# mcu_core.net
KiCad netlist of a schematic drawn in Altium Designer
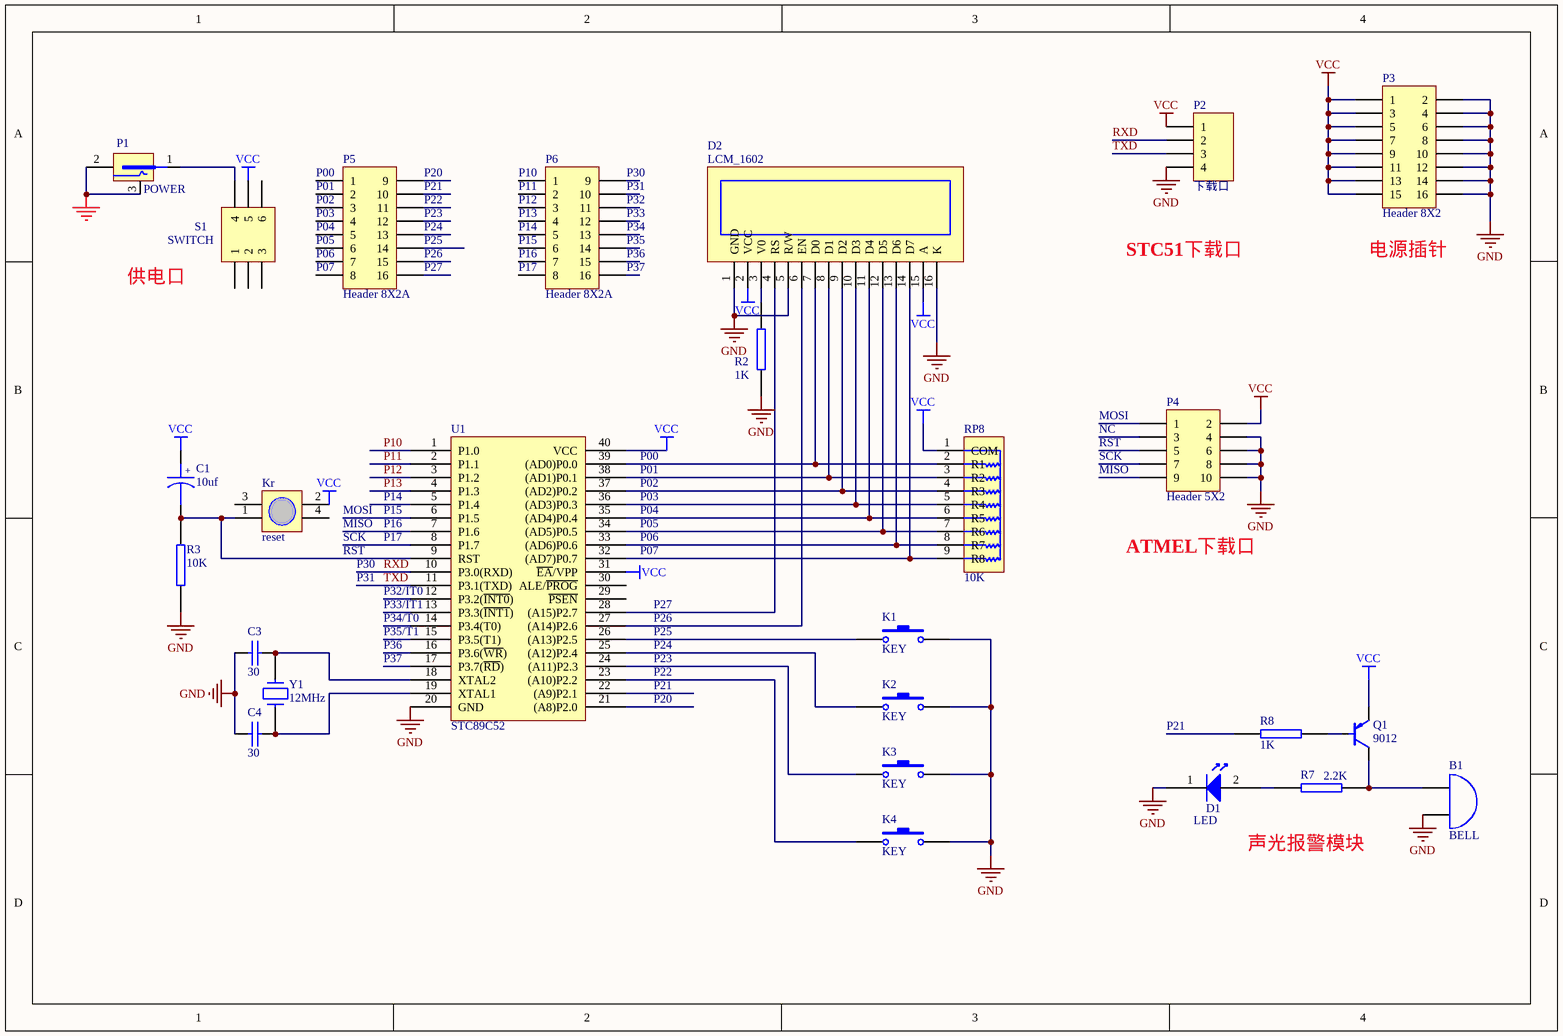
[diagram p0: mcu core.SchDoc]

(export (version "E")
  (design (tool "Eeschema 10.0.6"))
  (components
    (comp (ref "B1") (value "BELL") (footprint "bell") (libsource (lib "xinweidz") (part "BELL")))
    (comp (ref "C1")
      (value "10uf")
      (footprint "C4*7")
      (description "Capacitor")
      (libsource (lib "xinweidz") (part "电解电容"))
    )
    (comp (ref "C3")
      (value "30")
      (footprint "CAP-2.54")
      (description "Capacitor")
      (libsource (lib "*") (part "CAP"))
    )
    (comp (ref "C4")
      (value "30")
      (footprint "CAP-2.54")
      (description "Capacitor")
      (libsource (lib "*") (part "CAP"))
    )
    (comp (ref "D1") (value "LED") (footprint "LED5MM-RED") (libsource (lib "xinweidz") (part "LED5")))
    (comp (ref "D2") (value "LCM_1602") (footprint "HDR1X16") (libsource (lib "*") (part "LCM1602")))
    (comp (ref "K1")
      (value "KEY")
      (footprint "SW-0606")
      (fields (field (name "PUBLISHER") "Altium Limited"))
      (libsource (lib "BIG_PP") (part "KEY"))
    )
    (comp (ref "K2")
      (value "KEY")
      (footprint "SW-0606")
      (fields (field (name "PUBLISHER") "Altium Limited"))
      (libsource (lib "BIG_PP") (part "KEY"))
    )
    (comp (ref "K3")
      (value "KEY")
      (footprint "SW-0606")
      (fields (field (name "PUBLISHER") "Altium Limited"))
      (libsource (lib "BIG_PP") (part "KEY"))
    )
    (comp (ref "K4")
      (value "KEY")
      (footprint "SW-0606")
      (fields (field (name "PUBLISHER") "Altium Limited"))
      (libsource (lib "BIG_PP") (part "KEY"))
    )
    (comp (ref "Kr") (value "reset") (footprint "SW-0606") (libsource (lib "*") (part "KEY")))
    (comp (ref "P1") (value "POWER") (footprint "DC002") (libsource (lib "*") (part "POWER")))
    (comp (ref "P2")
      (value "下载口")
      (footprint "HDR1X4")
      (description "Header, 4-Pin, Right Angle")
      (fields (field (name "PUBLISHER") "Altium Limited"))
      (libsource (lib "BIG_PP") (part "Header 4H"))
    )
    (comp (ref "P3")
      (value "Header 8X2")
      (footprint "HDR2X8")
      (description "Header, 8-Pin, Dual row")
      (fields (field (name "PUBLISHER") "Altium Limited"))
      (libsource (lib "BIG_PP") (part "Header 8X2"))
    )
    (comp (ref "P4")
      (value "Header 5X2")
      (footprint "HDR2X5")
      (description "Header, 5-Pin, Dual row")
      (fields (field (name "PUBLISHER") "Altium Limited"))
      (libsource (lib "BIG_PP") (part "Header 5X2"))
    )
    (comp (ref "P5")
      (value "Header 8X2A")
      (footprint "HDR2X8_CEN")
      (description "Header, 8-Pin, Dual row")
      (fields (field (name "PUBLISHER") "Altium Limited"))
      (libsource (lib "BIG_PP") (part "Header 8X2A"))
    )
    (comp (ref "P6")
      (value "Header 8X2A")
      (footprint "HDR2X8_CEN")
      (description "Header, 8-Pin, Dual row")
      (fields (field (name "PUBLISHER") "Altium Limited"))
      (libsource (lib "BIG_PP") (part "Header 8X2A"))
    )
    (comp (ref "Q1") (value "9012") (footprint "TO-92A") (libsource (lib "xinweidz") (part "PNP")))
    (comp (ref "R2") (value "1K") (footprint "1/4W") (libsource (lib "*") (part "RES2")))
    (comp (ref "R3") (value "10K") (footprint "1/4W") (libsource (lib "*") (part "RES2")))
    (comp (ref "R7") (value "2.2K") (footprint "1/4W") (libsource (lib "*") (part "RES2")))
    (comp (ref "R8") (value "1K") (footprint "1/4W") (libsource (lib "*") (part "RES2")))
    (comp (ref "RP8") (value "10K") (footprint "R-9PIN") (libsource (lib "*") (part "RP8")))
    (comp (ref "S1")
      (value "SWITCH")
      (footprint "SW-8X8X8")
      (description "Header, 3-Pin, Dual row")
      (fields (field (name "PUBLISHER") "Altium Limited"))
      (libsource (lib "BIG_PP") (part "Header 3X2A"))
    )
    (comp (ref "U1") (value "STC89C52") (footprint "DIP40") (libsource (lib "*") (part "AT89C51")))
    (comp (ref "Y1")
      (value "12MHz")
      (footprint "XTAL-49/S_N")
      (description "Crystal")
      (libsource (lib "*") (part "CRYSTAL"))
    )
  )
  (nets
    (net (code "1") (name "/MISO") (class "Default")
      (node (ref "P4") (pin "9") (pinfunction "9_9") (pintype "passive"))
      (node (ref "P6") (pin "7") (pinfunction "7_7") (pintype "passive"))
      (node (ref "U1") (pin "7") (pinfunction "P1.6_7") (pintype "passive"))
    )
    (net (code "2") (name "/MOSI") (class "Default")
      (node (ref "P4") (pin "1") (pinfunction "1_1") (pintype "passive"))
      (node (ref "P6") (pin "6") (pinfunction "6_6") (pintype "passive"))
      (node (ref "U1") (pin "6") (pinfunction "P1.5_6") (pintype "passive"))
    )
    (net (code "3") (name "/NC") (class "Default")
      (node (ref "P4") (pin "3") (pinfunction "3_3") (pintype "passive"))
    )
    (net (code "4") (name "/P00") (class "Default")
      (node (ref "D2") (pin "7") (pinfunction "D0_7") (pintype "passive"))
      (node (ref "P5") (pin "1") (pinfunction "1_1") (pintype "passive"))
      (node (ref "RP8") (pin "2") (pinfunction "R1_2") (pintype "passive"))
      (node (ref "U1") (pin "39") (pinfunction "(AD0)P0.0_39") (pintype "passive"))
    )
    (net (code "5") (name "/P01") (class "Default")
      (node (ref "D2") (pin "8") (pinfunction "D1_8") (pintype "passive"))
      (node (ref "P5") (pin "2") (pinfunction "2_2") (pintype "passive"))
      (node (ref "RP8") (pin "3") (pinfunction "R2_3") (pintype "passive"))
      (node (ref "U1") (pin "38") (pinfunction "(AD1)P0.1_38") (pintype "passive"))
    )
    (net (code "6") (name "/P02") (class "Default")
      (node (ref "D2") (pin "9") (pinfunction "D2_9") (pintype "passive"))
      (node (ref "P5") (pin "3") (pinfunction "3_3") (pintype "passive"))
      (node (ref "RP8") (pin "4") (pinfunction "R3_4") (pintype "passive"))
      (node (ref "U1") (pin "37") (pinfunction "(AD2)P0.2_37") (pintype "passive"))
    )
    (net (code "7") (name "/P03") (class "Default")
      (node (ref "D2") (pin "10") (pinfunction "D3_10") (pintype "passive"))
      (node (ref "P5") (pin "4") (pinfunction "4_4") (pintype "passive"))
      (node (ref "RP8") (pin "5") (pinfunction "R4_5") (pintype "passive"))
      (node (ref "U1") (pin "36") (pinfunction "(AD3)P0.3_36") (pintype "passive"))
    )
    (net (code "8") (name "/P04") (class "Default")
      (node (ref "D2") (pin "11") (pinfunction "D4_11") (pintype "passive"))
      (node (ref "P5") (pin "5") (pinfunction "5_5") (pintype "passive"))
      (node (ref "RP8") (pin "6") (pinfunction "R5_6") (pintype "passive"))
      (node (ref "U1") (pin "35") (pinfunction "(AD4)P0.4_35") (pintype "passive"))
    )
    (net (code "9") (name "/P05") (class "Default")
      (node (ref "D2") (pin "12") (pinfunction "D5_12") (pintype "passive"))
      (node (ref "P5") (pin "6") (pinfunction "6_6") (pintype "passive"))
      (node (ref "RP8") (pin "7") (pinfunction "R6_7") (pintype "passive"))
      (node (ref "U1") (pin "34") (pinfunction "(AD5)P0.5_34") (pintype "passive"))
    )
    (net (code "10") (name "/P06") (class "Default")
      (node (ref "D2") (pin "13") (pinfunction "D6_13") (pintype "passive"))
      (node (ref "P5") (pin "7") (pinfunction "7_7") (pintype "passive"))
      (node (ref "RP8") (pin "8") (pinfunction "R7_8") (pintype "passive"))
      (node (ref "U1") (pin "33") (pinfunction "(AD6)P0.6_33") (pintype "passive"))
    )
    (net (code "11") (name "/P07") (class "Default")
      (node (ref "D2") (pin "14") (pinfunction "D7_14") (pintype "passive"))
      (node (ref "P5") (pin "8") (pinfunction "8_8") (pintype "passive"))
      (node (ref "RP8") (pin "9") (pinfunction "R8_9") (pintype "passive"))
      (node (ref "U1") (pin "32") (pinfunction "(AD7)P0.7_32") (pintype "passive"))
    )
    (net (code "12") (name "/P10") (class "Default")
      (node (ref "P6") (pin "1") (pinfunction "1_1") (pintype "passive"))
      (node (ref "U1") (pin "1") (pinfunction "P1.0_1") (pintype "passive"))
    )
    (net (code "13") (name "/P11") (class "Default")
      (node (ref "P6") (pin "2") (pinfunction "2_2") (pintype "passive"))
      (node (ref "U1") (pin "2") (pinfunction "P1.1_2") (pintype "passive"))
    )
    (net (code "14") (name "/P12") (class "Default")
      (node (ref "P6") (pin "3") (pinfunction "3_3") (pintype "passive"))
      (node (ref "U1") (pin "3") (pinfunction "P1.2_3") (pintype "passive"))
    )
    (net (code "15") (name "/P13") (class "Default")
      (node (ref "P6") (pin "4") (pinfunction "4_4") (pintype "passive"))
      (node (ref "U1") (pin "4") (pinfunction "P1.3_4") (pintype "passive"))
    )
    (net (code "16") (name "/P14") (class "Default")
      (node (ref "P6") (pin "5") (pinfunction "5_5") (pintype "passive"))
      (node (ref "U1") (pin "5") (pinfunction "P1.4_5") (pintype "passive"))
    )
    (net (code "17") (name "/P17") (class "Default")
      (node (ref "P4") (pin "7") (pinfunction "7_7") (pintype "passive"))
      (node (ref "P6") (pin "8") (pinfunction "8_8") (pintype "passive"))
      (node (ref "U1") (pin "8") (pinfunction "P1.7_8") (pintype "passive"))
    )
    (net (code "18") (name "/P20") (class "Default")
      (node (ref "P5") (pin "9") (pinfunction "9_9") (pintype "passive"))
      (node (ref "U1") (pin "21") (pinfunction "(A8)P2.0_21") (pintype "passive"))
    )
    (net (code "19") (name "/P21") (class "Default")
      (node (ref "P5") (pin "10") (pinfunction "10_10") (pintype "passive"))
      (node (ref "R8") (pin "2") (pinfunction "2_2") (pintype "passive"))
      (node (ref "U1") (pin "22") (pinfunction "(A9)P2.1_22") (pintype "passive"))
    )
    (net (code "20") (name "/P22") (class "Default")
      (node (ref "K4") (pin "1") (pinfunction "1_1") (pintype "passive"))
      (node (ref "P5") (pin "11") (pinfunction "11_11") (pintype "passive"))
      (node (ref "U1") (pin "23") (pinfunction "(A10)P2.2_23") (pintype "passive"))
    )
    (net (code "21") (name "/P23") (class "Default")
      (node (ref "K3") (pin "1") (pinfunction "1_1") (pintype "passive"))
      (node (ref "P5") (pin "12") (pinfunction "12_12") (pintype "passive"))
      (node (ref "U1") (pin "24") (pinfunction "(A11)P2.3_24") (pintype "passive"))
    )
    (net (code "22") (name "/P24") (class "Default")
      (node (ref "K2") (pin "1") (pinfunction "1_1") (pintype "passive"))
      (node (ref "P5") (pin "13") (pinfunction "13_13") (pintype "passive"))
      (node (ref "U1") (pin "25") (pinfunction "(A12)P2.4_25") (pintype "passive"))
    )
    (net (code "23") (name "/P25") (class "Default")
      (node (ref "K1") (pin "1") (pinfunction "1_1") (pintype "passive"))
      (node (ref "P5") (pin "14") (pinfunction "14_14") (pintype "passive"))
      (node (ref "U1") (pin "26") (pinfunction "(A13)P2.5_26") (pintype "passive"))
    )
    (net (code "24") (name "/P26") (class "Default")
      (node (ref "D2") (pin "6") (pinfunction "EN_6") (pintype "passive"))
      (node (ref "P5") (pin "15") (pinfunction "15_15") (pintype "passive"))
      (node (ref "U1") (pin "27") (pinfunction "(A14)P2.6_27") (pintype "passive"))
    )
    (net (code "25") (name "/P27") (class "Default")
      (node (ref "D2") (pin "4") (pinfunction "RS_4") (pintype "passive"))
      (node (ref "P5") (pin "16") (pinfunction "16_16") (pintype "passive"))
      (node (ref "U1") (pin "28") (pinfunction "(A15)P2.7_28") (pintype "passive"))
    )
    (net (code "26") (name "/P30") (class "Default")
      (node (ref "P2") (pin "2") (pinfunction "2_2") (pintype "passive"))
      (node (ref "P6") (pin "9") (pinfunction "9_9") (pintype "passive"))
      (node (ref "U1") (pin "10") (pinfunction "P3.0(RXD)_10") (pintype "passive"))
    )
    (net (code "27") (name "/P31") (class "Default")
      (node (ref "P2") (pin "3") (pinfunction "3_3") (pintype "passive"))
      (node (ref "P6") (pin "10") (pinfunction "10_10") (pintype "passive"))
      (node (ref "U1") (pin "11") (pinfunction "P3.1(TXD)_11") (pintype "passive"))
    )
    (net (code "28") (name "/P32") (class "Default")
      (node (ref "P6") (pin "11") (pinfunction "11_11") (pintype "passive"))
    )
    (net (code "29") (name "/P32{slash}IT0") (class "Default")
      (node (ref "U1") (pin "12") (pinfunction "P3.2(~{INT0})_12") (pintype "passive"))
    )
    (net (code "30") (name "/P33") (class "Default")
      (node (ref "P6") (pin "12") (pinfunction "12_12") (pintype "passive"))
    )
    (net (code "31") (name "/P33{slash}IT1") (class "Default")
      (node (ref "U1") (pin "13") (pinfunction "P3.3(~{INT1})_13") (pintype "passive"))
    )
    (net (code "32") (name "/P34") (class "Default")
      (node (ref "P6") (pin "13") (pinfunction "13_13") (pintype "passive"))
    )
    (net (code "33") (name "/P34{slash}T0") (class "Default")
      (node (ref "U1") (pin "14") (pinfunction "P3.4(T0)_14") (pintype "passive"))
    )
    (net (code "34") (name "/P35") (class "Default")
      (node (ref "P6") (pin "14") (pinfunction "14_14") (pintype "passive"))
    )
    (net (code "35") (name "/P35{slash}T1") (class "Default")
      (node (ref "U1") (pin "15") (pinfunction "P3.5(T1)_15") (pintype "passive"))
    )
    (net (code "36") (name "/P36") (class "Default")
      (node (ref "P6") (pin "15") (pinfunction "15_15") (pintype "passive"))
      (node (ref "U1") (pin "16") (pinfunction "P3.6(~{WR})_16") (pintype "passive"))
    )
    (net (code "37") (name "/P37") (class "Default")
      (node (ref "P6") (pin "16") (pinfunction "16_16") (pintype "passive"))
      (node (ref "U1") (pin "17") (pinfunction "P3.7(~{RD})_17") (pintype "passive"))
    )
    (net (code "38") (name "/RST") (class "Default")
      (node (ref "C1") (pin "1") (pinfunction "1_1") (pintype "passive"))
      (node (ref "Kr") (pin "1") (pintype "passive"))
      (node (ref "P4") (pin "5") (pinfunction "5_5") (pintype "passive"))
      (node (ref "R3") (pin "2") (pinfunction "2_2") (pintype "passive"))
      (node (ref "U1") (pin "9") (pinfunction "RST_9") (pintype "passive"))
    )
    (net (code "39") (name "GND") (class "Default")
      (node (ref "B1") (pin "2") (pinfunction "2_2") (pintype "passive"))
      (node (ref "C3") (pin "2") (pinfunction "2_2") (pintype "passive"))
      (node (ref "C4") (pin "2") (pinfunction "2_2") (pintype "passive"))
      (node (ref "D1") (pin "1") (pinfunction "1_1") (pintype "passive"))
      (node (ref "D2") (pin "1") (pinfunction "GND_1") (pintype "passive"))
      (node (ref "D2") (pin "16") (pinfunction "K_16") (pintype "passive"))
      (node (ref "D2") (pin "5") (pinfunction "R/W_5") (pintype "passive"))
      (node (ref "K1") (pin "2") (pinfunction "2_2") (pintype "passive"))
      (node (ref "K2") (pin "2") (pinfunction "2_2") (pintype "passive"))
      (node (ref "K3") (pin "2") (pinfunction "2_2") (pintype "passive"))
      (node (ref "K4") (pin "2") (pinfunction "2_2") (pintype "passive"))
      (node (ref "P1") (pin "2") (pintype "passive"))
      (node (ref "P1") (pin "3") (pintype "passive"))
      (node (ref "P2") (pin "4") (pinfunction "4_4") (pintype "passive"))
      (node (ref "P3") (pin "10") (pinfunction "10_10") (pintype "passive"))
      (node (ref "P3") (pin "12") (pinfunction "12_12") (pintype "passive"))
      (node (ref "P3") (pin "14") (pinfunction "14_14") (pintype "passive"))
      (node (ref "P3") (pin "16") (pinfunction "16_16") (pintype "passive"))
      (node (ref "P3") (pin "2") (pinfunction "2_2") (pintype "passive"))
      (node (ref "P3") (pin "4") (pinfunction "4_4") (pintype "passive"))
      (node (ref "P3") (pin "6") (pinfunction "6_6") (pintype "passive"))
      (node (ref "P3") (pin "8") (pinfunction "8_8") (pintype "passive"))
      (node (ref "P4") (pin "10") (pinfunction "10_10") (pintype "passive"))
      (node (ref "P4") (pin "4") (pinfunction "4_4") (pintype "passive"))
      (node (ref "P4") (pin "6") (pinfunction "6_6") (pintype "passive"))
      (node (ref "P4") (pin "8") (pinfunction "8_8") (pintype "passive"))
      (node (ref "R2") (pin "1") (pinfunction "1_1") (pintype "passive"))
      (node (ref "R3") (pin "1") (pinfunction "1_1") (pintype "passive"))
      (node (ref "U1") (pin "20") (pinfunction "GND_20") (pintype "passive"))
    )
    (net (code "40") (name "Net-(D1-Pad2)") (class "Default")
      (node (ref "D1") (pin "2") (pinfunction "2_2") (pintype "passive"))
      (node (ref "R7") (pin "2") (pinfunction "2_2") (pintype "passive"))
    )
    (net (code "41") (name "Net-(D2-V0)") (class "Default")
      (node (ref "D2") (pin "3") (pinfunction "V0_3") (pintype "passive"))
      (node (ref "R2") (pin "2") (pinfunction "2_2") (pintype "passive"))
    )
    (net (code "42") (name "Net-(P1-Pad1)") (class "Default")
      (node (ref "P1") (pin "1") (pintype "passive"))
      (node (ref "S1") (pin "4") (pinfunction "4_4") (pintype "passive"))
    )
    (net (code "43") (name "Net-(Q1-b)") (class "Default")
      (node (ref "Q1") (pin "2") (pinfunction "b_2") (pintype "passive"))
      (node (ref "R8") (pin "1") (pinfunction "1_1") (pintype "passive"))
    )
    (net (code "44") (name "Net-(Q1-c)") (class "Default")
      (node (ref "B1") (pin "1") (pinfunction "1_1") (pintype "passive"))
      (node (ref "Q1") (pin "3") (pinfunction "c_3") (pintype "passive"))
      (node (ref "R7") (pin "1") (pinfunction "1_1") (pintype "passive"))
    )
    (net (code "45") (name "Net-(U1-XTAL1)") (class "Default")
      (node (ref "C4") (pin "1") (pinfunction "1_1") (pintype "passive"))
      (node (ref "U1") (pin "19") (pinfunction "XTAL1_19") (pintype "passive"))
      (node (ref "Y1") (pin "2") (pinfunction "2_2") (pintype "passive"))
    )
    (net (code "46") (name "Net-(U1-XTAL2)") (class "Default")
      (node (ref "C3") (pin "1") (pinfunction "1_1") (pintype "passive"))
      (node (ref "U1") (pin "18") (pinfunction "XTAL2_18") (pintype "passive"))
      (node (ref "Y1") (pin "1") (pinfunction "1_1") (pintype "passive"))
    )
    (net (code "47") (name "VCC") (class "Default")
      (node (ref "C1") (pin "2") (pinfunction "2_2") (pintype "passive"))
      (node (ref "D2") (pin "15") (pinfunction "A_15") (pintype "passive"))
      (node (ref "D2") (pin "2") (pinfunction "VCC_2") (pintype "passive"))
      (node (ref "Kr") (pin "2") (pintype "passive"))
      (node (ref "P2") (pin "1") (pinfunction "1_1") (pintype "passive"))
      (node (ref "P3") (pin "1") (pinfunction "1_1") (pintype "passive"))
      (node (ref "P3") (pin "11") (pinfunction "11_11") (pintype "passive"))
      (node (ref "P3") (pin "13") (pinfunction "13_13") (pintype "passive"))
      (node (ref "P3") (pin "15") (pinfunction "15_15") (pintype "passive"))
      (node (ref "P3") (pin "3") (pinfunction "3_3") (pintype "passive"))
      (node (ref "P3") (pin "5") (pinfunction "5_5") (pintype "passive"))
      (node (ref "P3") (pin "7") (pinfunction "7_7") (pintype "passive"))
      (node (ref "P3") (pin "9") (pinfunction "9_9") (pintype "passive"))
      (node (ref "P4") (pin "2") (pinfunction "2_2") (pintype "passive"))
      (node (ref "Q1") (pin "1") (pinfunction "e_1") (pintype "passive"))
      (node (ref "RP8") (pin "1") (pinfunction "COM_1") (pintype "passive"))
      (node (ref "S1") (pin "5") (pinfunction "5_5") (pintype "passive"))
      (node (ref "U1") (pin "31") (pinfunction "~{EA}/VPP_31") (pintype "passive"))
      (node (ref "U1") (pin "40") (pinfunction "VCC_40") (pintype "passive"))
    )
    (net (code "48") (name "unconnected-(Kr-Pad3)") (class "Default")
      (node (ref "Kr") (pin "3") (pintype "passive"))
    )
    (net (code "49") (name "unconnected-(Kr-Pad4)") (class "Default")
      (node (ref "Kr") (pin "4") (pintype "passive"))
    )
    (net (code "50") (name "unconnected-(S1-Pad1)") (class "Default")
      (node (ref "S1") (pin "1") (pinfunction "1_1") (pintype "passive"))
    )
    (net (code "51") (name "unconnected-(S1-Pad2)") (class "Default")
      (node (ref "S1") (pin "2") (pinfunction "2_2") (pintype "passive"))
    )
    (net (code "52") (name "unconnected-(S1-Pad3)") (class "Default")
      (node (ref "S1") (pin "3") (pinfunction "3_3") (pintype "passive"))
    )
    (net (code "53") (name "unconnected-(S1-Pad6)") (class "Default")
      (node (ref "S1") (pin "6") (pinfunction "6_6") (pintype "passive"))
    )
    (net (code "54") (name "unconnected-(U1-ALE{slash}~{PROG}-Pad30)") (class "Default")
      (node (ref "U1") (pin "30") (pinfunction "ALE/~{PROG}_30") (pintype "passive"))
    )
    (net (code "55") (name "unconnected-(U1-~{PSEN}-Pad29)") (class "Default")
      (node (ref "U1") (pin "29") (pinfunction "~{PSEN}_29") (pintype "passive"))
    )
  )
)
